# ProPrj__B__2024-10-28.net
KiCad netlist of a schematic drawn in EasyEDA Pro
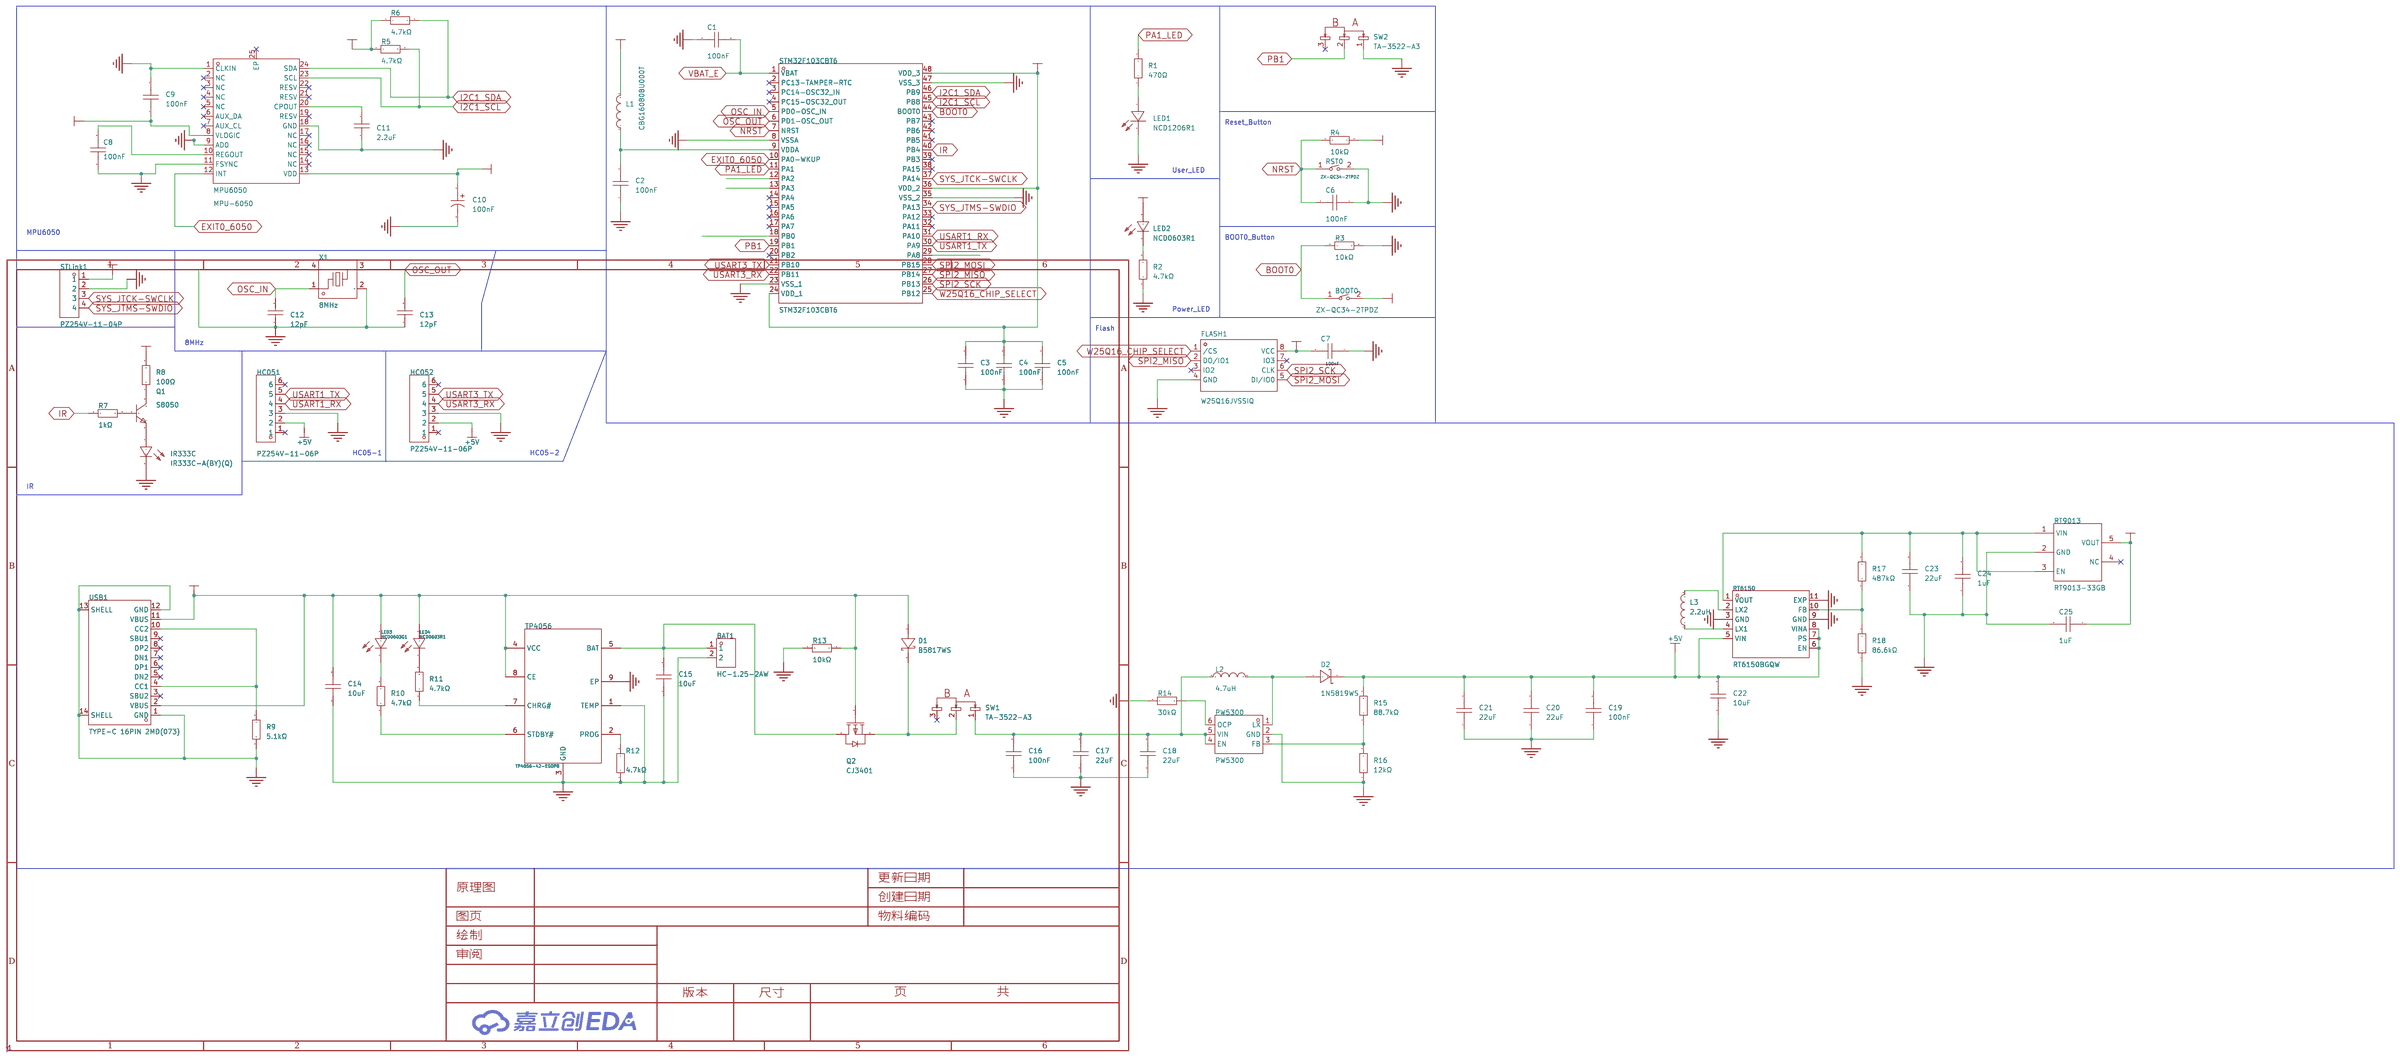
[diagram p0: schematic sheet]

(export (version "E")
  (design (tool "Eeschema 10.0.6"))
  (components
    (comp (ref "BAT1")
      (value "HC-1.25-2AW")
      (footprint "easyedapro:CONN-TH_2P-P1.25_HCTL_HC-1.25-2AW")
      (fields (field (name "Manufacturer") "HCTL(华灿天禄)"))
      (libsource (lib "easyedapro") (part "HC-1.25-2AW"))
    )
    (comp (ref "BOOT0")
      (value "ZX-QC34-2TPDZ")
      (footprint "easyedapro:KEY-SMD_L3.9-W3.0-LS5.0-EH")
      (fields (field (name "Manufacturer") "Megastar(兆星)"))
      (libsource (lib "easyedapro") (part "ZX-QC34-2TPDZ"))
    )
    (comp (ref "C1")
      (value "100nF")
      (footprint "easyedapro:C0603")
      (description "容值:100nF;精度:±10%;额定电压:50V;材质(温度系数):X7R;")
      (fields
        (field (name "Manufacturer Part") "CC0603KRX7R9BB104")
        (field (name "Manufacturer") "YAGEO(国巨)")
      )
      (libsource (lib "easyedapro") (part "CC0603KRX7R9BB104"))
    )
    (comp (ref "C2")
      (value "100nF")
      (footprint "easyedapro:C0603")
      (description "容值:100nF;精度:±10%;额定电压:50V;材质(温度系数):X7R;")
      (fields
        (field (name "Manufacturer Part") "CC0603KRX7R9BB104")
        (field (name "Manufacturer") "YAGEO(国巨)")
      )
      (libsource (lib "easyedapro") (part "CC0603KRX7R9BB104"))
    )
    (comp (ref "C3")
      (value "100nF")
      (footprint "easyedapro:C0603")
      (description "容值:100nF;精度:±10%;额定电压:50V;材质(温度系数):X7R;")
      (fields
        (field (name "Manufacturer Part") "CC0603KRX7R9BB104")
        (field (name "Manufacturer") "YAGEO(国巨)")
      )
      (libsource (lib "easyedapro") (part "CC0603KRX7R9BB104"))
    )
    (comp (ref "C4")
      (value "100nF")
      (footprint "easyedapro:C0603")
      (description "容值:100nF;精度:±10%;额定电压:50V;材质(温度系数):X7R;")
      (fields
        (field (name "Manufacturer Part") "CC0603KRX7R9BB104")
        (field (name "Manufacturer") "YAGEO(国巨)")
      )
      (libsource (lib "easyedapro") (part "CC0603KRX7R9BB104"))
    )
    (comp (ref "C5")
      (value "100nF")
      (footprint "easyedapro:C0603")
      (description "容值:100nF;精度:±10%;额定电压:50V;材质(温度系数):X7R;")
      (fields
        (field (name "Manufacturer Part") "CC0603KRX7R9BB104")
        (field (name "Manufacturer") "YAGEO(国巨)")
      )
      (libsource (lib "easyedapro") (part "CC0603KRX7R9BB104"))
    )
    (comp (ref "C6")
      (value "100nF")
      (footprint "easyedapro:C0603")
      (description "容值:100nF;精度:±10%;额定电压:50V;材质(温度系数):X7R;")
      (fields
        (field (name "Manufacturer Part") "CC0603KRX7R9BB104")
        (field (name "Manufacturer") "YAGEO(国巨)")
      )
      (libsource (lib "easyedapro") (part "CC0603KRX7R9BB104"))
    )
    (comp (ref "C7")
      (value "100nF")
      (footprint "easyedapro:C0603")
      (description "容值:100nF;精度:±10%;额定电压:50V;材质(温度系数):X7R;")
      (fields
        (field (name "Manufacturer Part") "CC0603KRX7R9BB104")
        (field (name "Manufacturer") "YAGEO(国巨)")
      )
      (libsource (lib "easyedapro") (part "CC0603KRX7R9BB104"))
    )
    (comp (ref "C8")
      (value "100nF")
      (footprint "easyedapro:C0603")
      (description "容值:100nF;精度:±10%;额定电压:50V;材质(温度系数):X7R;")
      (fields
        (field (name "Manufacturer Part") "CC0603KRX7R9BB104")
        (field (name "Manufacturer") "YAGEO(国巨)")
      )
      (libsource (lib "easyedapro") (part "CC0603KRX7R9BB104"))
    )
    (comp (ref "C9")
      (value "100nF")
      (footprint "easyedapro:C0603")
      (description "容值:100nF;精度:±10%;额定电压:50V;材质(温度系数):X7R;")
      (fields
        (field (name "Manufacturer Part") "CC0603KRX7R9BB104")
        (field (name "Manufacturer") "YAGEO(国巨)")
      )
      (libsource (lib "easyedapro") (part "CC0603KRX7R9BB104"))
    )
    (comp (ref "C10")
      (value "100nF")
      (footprint "easyedapro:CAP-SMD_L3.2-W1.6-FD")
      (description "容值:100nF;精度:±20%;额定电压:50V;等效串联电阻:20Ω;")
      (fields (field (name "Manufacturer Part") "T491A104M050AT") (field (name "Manufacturer") "KEMET(基美)"))
      (libsource (lib "easyedapro") (part "T491A104M050AT"))
    )
    (comp (ref "C11")
      (value "2.2uF")
      (footprint "easyedapro:C0603")
      (description "容值:2.2uF;精度:±10%;额定电压:16V;材质(温度系数):X5R;")
      (fields
        (field (name "Manufacturer Part") "CL10A225KO8NNNC")
        (field (name "Manufacturer") "SAMSUNG(三星)")
      )
      (libsource (lib "easyedapro") (part "CL10A225KO8NNNC"))
    )
    (comp (ref "C12")
      (value "12pF")
      (footprint "easyedapro:C0603")
      (description "容值:12pF;精度:±5%;额定电压:50V;材质(温度系数):C0G;")
      (fields
        (field (name "Manufacturer Part") "CL10C120JB8NNNC")
        (field (name "Manufacturer") "SAMSUNG(三星)")
      )
      (libsource (lib "easyedapro") (part "CL10C120JB8NNNC"))
    )
    (comp (ref "C13")
      (value "12pF")
      (footprint "easyedapro:C0603")
      (description "容值:12pF;精度:±5%;额定电压:50V;材质(温度系数):C0G;")
      (fields
        (field (name "Manufacturer Part") "CL10C120JB8NNNC")
        (field (name "Manufacturer") "SAMSUNG(三星)")
      )
      (libsource (lib "easyedapro") (part "CL10C120JB8NNNC"))
    )
    (comp (ref "C14")
      (value "10uF")
      (footprint "easyedapro:C0603")
      (description "容值:10uF;精度:±20%;额定电压:16V;材质(温度系数):X5R;")
      (fields
        (field (name "Manufacturer Part") "HGC0603R5106M160NTHJ")
        (field (name "Manufacturer") "Chinocera(华瓷)")
      )
      (libsource (lib "easyedapro") (part "HGC0603R5106M160NTHJ"))
    )
    (comp (ref "C15")
      (value "10uF")
      (footprint "easyedapro:C0603")
      (description "容值:10uF;精度:±20%;额定电压:16V;材质(温度系数):X5R;")
      (fields
        (field (name "Manufacturer Part") "HGC0603R5106M160NTHJ")
        (field (name "Manufacturer") "Chinocera(华瓷)")
      )
      (libsource (lib "easyedapro") (part "HGC0603R5106M160NTHJ"))
    )
    (comp (ref "C16")
      (value "100nF")
      (footprint "easyedapro:C0603")
      (description "容值:100nF;精度:±10%;额定电压:50V;材质(温度系数):X7R;")
      (fields
        (field (name "Manufacturer Part") "CGA0603X7R104K500JT")
        (field (name "Manufacturer") "HRE(芯声)")
      )
      (libsource (lib "easyedapro") (part "cga0603x7r104k500jt"))
    )
    (comp (ref "C17")
      (value "22uF")
      (footprint "easyedapro:C0805")
      (description "容值:22uF;精度:±20%;额定电压:35V;材质(温度系数):X5R;")
      (fields
        (field (name "Manufacturer Part") "CGA0603X5R226M160JT")
        (field (name "Manufacturer") "HRE(芯声)")
      )
      (libsource (lib "easyedapro") (part "CGA0805X5R226M350MT"))
    )
    (comp (ref "C18")
      (value "22uF")
      (footprint "easyedapro:C0805")
      (description "容值:22uF;精度:±20%;额定电压:35V;材质(温度系数):X5R;")
      (fields
        (field (name "Manufacturer Part") "CGA0603X5R226M160JT")
        (field (name "Manufacturer") "HRE(芯声)")
      )
      (libsource (lib "easyedapro") (part "CGA0805X5R226M350MT"))
    )
    (comp (ref "C19")
      (value "100nF")
      (footprint "easyedapro:C0603")
      (description "容值:100nF;精度:±10%;额定电压:50V;材质(温度系数):X7R;")
      (fields
        (field (name "Manufacturer Part") "CGA0603X7R104K500JT")
        (field (name "Manufacturer") "HRE(芯声)")
      )
      (libsource (lib "easyedapro") (part "cga0603x7r104k500jt"))
    )
    (comp (ref "C20")
      (value "22uF")
      (footprint "easyedapro:C0805")
      (description "容值:22uF;精度:±20%;额定电压:35V;材质(温度系数):X5R;")
      (fields
        (field (name "Manufacturer Part") "CGA0603X5R226M160JT")
        (field (name "Manufacturer") "HRE(芯声)")
      )
      (libsource (lib "easyedapro") (part "CGA0805X5R226M350MT"))
    )
    (comp (ref "C21")
      (value "22uF")
      (footprint "easyedapro:C0805")
      (description "容值:22uF;精度:±20%;额定电压:35V;材质(温度系数):X5R;")
      (fields
        (field (name "Manufacturer Part") "CGA0603X5R226M160JT")
        (field (name "Manufacturer") "HRE(芯声)")
      )
      (libsource (lib "easyedapro") (part "CGA0805X5R226M350MT"))
    )
    (comp (ref "C22")
      (value "10uF")
      (footprint "easyedapro:C0603")
      (description "容值:10uF;精度:±20%;额定电压:16V;材质(温度系数):X5R;")
      (fields
        (field (name "Manufacturer Part") "HGC0603R5106M160NTHJ")
        (field (name "Manufacturer") "Chinocera(华瓷)")
      )
      (libsource (lib "easyedapro") (part "HGC0603R5106M160NTHJ"))
    )
    (comp (ref "C23")
      (value "22uF")
      (footprint "easyedapro:C0603")
      (description "容值:22uF;精度:±20%;额定电压:16V;材质(温度系数):X5R;")
      (fields
        (field (name "Manufacturer Part") "CGA0603X5R226M160JT")
        (field (name "Manufacturer") "HRE(芯声)")
      )
      (libsource (lib "easyedapro") (part "CGA0603X5R226M160JT"))
    )
    (comp (ref "C24")
      (value "1uF")
      (footprint "easyedapro:C0603")
      (description "容值:1uF;精度:±10%;额定电压:16V;材质(温度系数):X5R;")
      (fields
        (field (name "Manufacturer Part") "CGA0603X5R105K160JT")
        (field (name "Manufacturer") "HRE(芯声)")
      )
      (libsource (lib "easyedapro") (part "CGA0603X5R105K160JT"))
    )
    (comp (ref "C25")
      (value "1uF")
      (footprint "easyedapro:C0603")
      (description "容值:1uF;精度:±10%;额定电压:16V;材质(温度系数):X5R;")
      (fields
        (field (name "Manufacturer Part") "CGA0603X5R105K160JT")
        (field (name "Manufacturer") "HRE(芯声)")
      )
      (libsource (lib "easyedapro") (part "CGA0603X5R105K160JT"))
    )
    (comp (ref "D1")
      (value "B5817WS")
      (footprint "easyedapro:SOD-323_L1.7-W1.3-LS2.5-FD")
      (description "二极管配置:独立式;正向压降(Vf):450mV@1.0A;直流反向耐压(Vr):20V;平均整流电流(Io):1A;")
      (fields (field (name "Manufacturer") "宏迦橙"))
      (libsource (lib "easyedapro") (part "B5817WS_C7420329"))
    )
    (comp (ref "D2")
      (value "1N5819WS")
      (footprint "easyedapro:SMB_L4.6-W3.6-LS5.3-RD")
      (description "正向压降(Vf):500mV@3A;直流反向耐压(Vr):40V;平均整流电流(Io):3A;")
      (fields (field (name "Manufacturer") "Hottech(合科泰)"))
      (libsource (lib "easyedapro") (part "SS34_C266556"))
    )
    (comp (ref "FLASH1")
      (value "W25Q16JVSSIQ")
      (footprint "easyedapro:SOIC-8_L5.3-W5.3-P1.27-LS8.0-BL")
      (description "（与C82317为同一颗物料，只是编带方式不一样。）3V 16Mbit Serial Flash Memory with dual/quad SPI")
      (fields (field (name "Manufacturer") "WINBOND(华邦)"))
      (libsource (lib "easyedapro") (part "W25Q16JVSSIQTR"))
    )
    (comp (ref "HC051")
      (value "PZ254V-11-06P")
      (footprint "easyedapro:HDR-TH_6P-P2.54-V-M")
      (fields (field (name "Manufacturer") "XFCN(兴飞)"))
      (libsource (lib "easyedapro") (part "PZ254V-11-06P"))
    )
    (comp (ref "HC052")
      (value "PZ254V-11-06P")
      (footprint "easyedapro:HDR-TH_6P-P2.54-V-M")
      (fields (field (name "Manufacturer") "XFCN(兴飞)"))
      (libsource (lib "easyedapro") (part "PZ254V-11-06P"))
    )
    (comp (ref "IR333C")
      (value "IR333C-A(BY)(Q)")
      (footprint "easyedapro:LED-TH_BD5.0-P2.54-FD")
      (description "波长:940nm;")
      (fields (field (name "Manufacturer") "EVERLIGHT(亿光)"))
      (libsource (lib "easyedapro") (part "ir333c-a(by)(q)"))
    )
    (comp (ref "L1")
      (value "CBG160808U000T")
      (footprint "easyedapro:L0603")
      (description "标称阻抗@测试频率:0Ω@100MHz;直流电阻(RDC):100mΩ;")
      (fields (field (name "Manufacturer") "FH(风华)"))
      (libsource (lib "easyedapro") (part "CBG160808U000T"))
    )
    (comp (ref "L2")
      (value "4.7uH")
      (footprint "easyedapro:IND-SMD_L5.4-W5.2_FXL0530")
      (description "电感值:4.7uH;精度:±20%;额定电流:4.5A;饱和电流(Isat):5A;类型:一体成型电感;")
      (fields
        (field (name "Manufacturer Part") "FTC252010S4R7MBCA")
        (field (name "Manufacturer") "cjiang(长江微电)")
      )
      (libsource (lib "easyedapro") (part "FXL0530-4R7-M"))
    )
    (comp (ref "L3")
      (value "2.2uH")
      (footprint "easyedapro:IND-SMD_L2.5-W2.0_MHCHL2520")
      (description "电感值:2.2uH;精度:±20%;额定电流:3A;饱和电流(Isat):3.8A;类型:一体成型电感;")
      (fields
        (field (name "Manufacturer Part") "FTC252012S2R2MBCA")
        (field (name "Manufacturer") "cjiang(长江微电)")
      )
      (libsource (lib "easyedapro") (part "FTC252012S2R2MBCA"))
    )
    (comp (ref "LED1")
      (value "NCD1206R1")
      (footprint "easyedapro:LED1206-R-RD_RED")
      (fields (field (name "Manufacturer") "国星光电"))
      (libsource (lib "easyedapro") (part "FC-3215HRK-620D"))
    )
    (comp (ref "LED2")
      (value "NCD0603R1")
      (footprint "easyedapro:LED0603-RD_RED")
      (fields (field (name "Manufacturer") "国星光电"))
      (libsource (lib "easyedapro") (part "FC-DA1608HRK-620D"))
    )
    (comp (ref "LED3")
      (value "NCD0603G1")
      (footprint "easyedapro:led0603-rd_1")
      (fields (field (name "Manufacturer") "国星光电"))
      (libsource (lib "easyedapro") (part "FC-D1608UGK-520D10"))
    )
    (comp (ref "LED4")
      (value "NCD0603R1")
      (footprint "easyedapro:led0603-rd_1")
      (fields (field (name "Manufacturer") "国星光电"))
      (libsource (lib "easyedapro") (part "FC-D1608UGK-520D10"))
    )
    (comp (ref "MPU6050")
      (value "MPU-6050")
      (footprint "easyedapro:QFN-24_L4.0-W4.0-P0.50-BL-EP2.7")
      (description "传感器类型:加速度计陀螺仪;")
      (fields (field (name "Manufacturer") "TDK InvenSense(应美盛)"))
      (libsource (lib "easyedapro") (part "MPU-6050_C24112"))
    )
    (comp (ref "PW5300")
      (value "PW5300")
      (footprint "easyedapro:SOT-23-6_L2.9-W1.6-P0.95-LS2.8-BL")
      (libsource (lib "easyedapro") (part "PW5300"))
    )
    (comp (ref "Q1")
      (value "S8050")
      (footprint "easyedapro:SOT-23-3_L2.9-W1.6-P1.90-LS2.8-BR")
      (description "晶体管类型:NPN;集电极电流(Ic):500mA;集射极击穿电压(Vceo):25V;功率(Pd):300mW;")
      (fields (field (name "Manufacturer") "Hottech(合科泰)"))
      (libsource (lib "easyedapro") (part "S8050_C181158"))
    )
    (comp (ref "Q2")
      (value "CJ3401")
      (footprint "easyedapro:SOT-23-3_L2.9-W1.6-P1.90-LS2.8-BR")
      (fields (field (name "Manufacturer") "CJ(江苏长电/长晶)"))
      (libsource (lib "easyedapro") (part "CJ3401"))
    )
    (comp (ref "R1")
      (value "470Ω")
      (footprint "easyedapro:R0603")
      (description "电阻类型:厚膜电阻;阻值:470Ω;精度:±1%;功率:100mW;最大工作电压:75V;温度系数:±100ppm/°C;")
      (fields
        (field (name "Manufacturer Part") "0603WAF4700T5E")
        (field (name "Manufacturer") "UNI-ROYAL(厚声)")
      )
      (libsource (lib "easyedapro") (part "0603WAF4700T5E"))
    )
    (comp (ref "R2")
      (value "4.7kΩ")
      (footprint "easyedapro:R0603")
      (description "电阻类型:厚膜电阻;阻值:4.7kΩ;精度:±1%;功率:100mW;最大工作电压:75V;温度系数:±100ppm/°C;")
      (fields
        (field (name "Manufacturer Part") "0603WAF4701T5E")
        (field (name "Manufacturer") "UNI-ROYAL(厚声)")
      )
      (libsource (lib "easyedapro") (part "0603WAF4701T5E"))
    )
    (comp (ref "R3")
      (value "10kΩ")
      (footprint "easyedapro:R0603")
      (description "电阻类型:厚膜电阻;阻值:10kΩ;精度:±1%;功率:100mW;最大工作电压:75V;温度系数:±100ppm/°C;")
      (fields
        (field (name "Manufacturer Part") "0603WAF1002T5E")
        (field (name "Manufacturer") "UNI-ROYAL(厚声)")
      )
      (libsource (lib "easyedapro") (part "0603WAF1002T5E"))
    )
    (comp (ref "R4")
      (value "10kΩ")
      (footprint "easyedapro:R0603")
      (description "电阻类型:厚膜电阻;阻值:10kΩ;精度:±1%;功率:100mW;最大工作电压:75V;温度系数:±100ppm/°C;")
      (fields
        (field (name "Manufacturer Part") "0603WAF1002T5E")
        (field (name "Manufacturer") "UNI-ROYAL(厚声)")
      )
      (libsource (lib "easyedapro") (part "0603WAF1002T5E"))
    )
    (comp (ref "R5")
      (value "4.7kΩ")
      (footprint "easyedapro:R0603")
      (description "电阻类型:厚膜电阻;阻值:4.7kΩ;精度:±1%;功率:100mW;最大工作电压:75V;温度系数:±100ppm/°C;")
      (fields
        (field (name "Manufacturer Part") "0603WAF4701T5E")
        (field (name "Manufacturer") "UNI-ROYAL(厚声)")
      )
      (libsource (lib "easyedapro") (part "0603WAF4701T5E"))
    )
    (comp (ref "R6")
      (value "4.7kΩ")
      (footprint "easyedapro:R0603")
      (description "电阻类型:厚膜电阻;阻值:4.7kΩ;精度:±1%;功率:100mW;最大工作电压:75V;温度系数:±100ppm/°C;")
      (fields
        (field (name "Manufacturer Part") "0603WAF4701T5E")
        (field (name "Manufacturer") "UNI-ROYAL(厚声)")
      )
      (libsource (lib "easyedapro") (part "0603WAF4701T5E"))
    )
    (comp (ref "R7")
      (value "1kΩ")
      (footprint "easyedapro:R0603")
      (description "电阻类型:厚膜电阻;阻值:1kΩ;精度:±1%;功率:100mW;最大工作电压:75V;温度系数:±100ppm/°C;")
      (fields
        (field (name "Manufacturer Part") "0603WAF1001T5E")
        (field (name "Manufacturer") "UNI-ROYAL(厚声)")
      )
      (libsource (lib "easyedapro") (part "0603WAF1001T5E"))
    )
    (comp (ref "R8")
      (value "100Ω")
      (footprint "easyedapro:R0603")
      (description "电阻类型:厚膜电阻;阻值:100Ω;精度:±1%;功率:100mW;最大工作电压:75V;温度系数:±200ppm/°C;")
      (fields
        (field (name "Manufacturer Part") "0603WAF1000T5E")
        (field (name "Manufacturer") "UNI-ROYAL(厚声)")
      )
      (libsource (lib "easyedapro") (part "0603WAF1000T5E"))
    )
    (comp (ref "R9")
      (value "5.1kΩ")
      (footprint "easyedapro:R0603")
      (description "电阻类型:厚膜电阻;阻值:5.1kΩ;精度:±1%;功率:100mW;最大工作电压:75V;温度系数:±100ppm/°C;")
      (fields
        (field (name "Manufacturer Part") "0603WAF5101T5E")
        (field (name "Manufacturer") "UNI-ROYAL(厚声)")
      )
      (libsource (lib "easyedapro") (part "0603WAF5101T5E"))
    )
    (comp (ref "R10")
      (value "4.7kΩ")
      (footprint "easyedapro:R0603")
      (description "电阻类型:厚膜电阻;阻值:4.7kΩ;精度:±1%;功率:100mW;最大工作电压:75V;温度系数:±100ppm/°C;")
      (fields
        (field (name "Manufacturer Part") "0603WAF4701T5E")
        (field (name "Manufacturer") "UNI-ROYAL(厚声)")
      )
      (libsource (lib "easyedapro") (part "0603WAF4701T5E"))
    )
    (comp (ref "R11")
      (value "4.7kΩ")
      (footprint "easyedapro:R0603")
      (description "电阻类型:厚膜电阻;阻值:4.7kΩ;精度:±1%;功率:100mW;最大工作电压:75V;温度系数:±100ppm/°C;")
      (fields
        (field (name "Manufacturer Part") "0603WAF4701T5E")
        (field (name "Manufacturer") "UNI-ROYAL(厚声)")
      )
      (libsource (lib "easyedapro") (part "0603WAF4701T5E"))
    )
    (comp (ref "R12")
      (value "4.7kΩ")
      (footprint "easyedapro:R0603")
      (description "电阻类型:厚膜电阻;阻值:4.7kΩ;精度:±1%;功率:100mW;最大工作电压:75V;温度系数:±100ppm/°C;")
      (fields
        (field (name "Manufacturer Part") "0603WAF4701T5E")
        (field (name "Manufacturer") "UNI-ROYAL(厚声)")
      )
      (libsource (lib "easyedapro") (part "0603WAF4701T5E"))
    )
    (comp (ref "R13")
      (value "10kΩ")
      (footprint "easyedapro:R0603")
      (description "电阻类型:厚膜电阻;阻值:10kΩ;精度:±1%;功率:100mW;最大工作电压:75V;温度系数:±100ppm/°C;")
      (fields
        (field (name "Manufacturer Part") "0603WAF1002T5E")
        (field (name "Manufacturer") "UNI-ROYAL(厚声)")
      )
      (libsource (lib "easyedapro") (part "0603WAF1002T5E"))
    )
    (comp (ref "R14")
      (value "30kΩ")
      (footprint "easyedapro:R0603")
      (description "电阻类型:厚膜电阻;阻值:30kΩ;精度:±1%;功率:100mW;最大工作电压:75V;温度系数:±100ppm/°C;")
      (fields
        (field (name "Manufacturer Part") "0603WAF3002T5E")
        (field (name "Manufacturer") "UNI-ROYAL(厚声)")
      )
      (libsource (lib "easyedapro") (part "0603WAF3002T5E"))
    )
    (comp (ref "R15")
      (value "88.7kΩ")
      (footprint "easyedapro:R0603")
      (fields (field (name "Manufacturer Part") "RCT0388K7FLF") (field (name "Manufacturer") "HKR(香港电阻)"))
      (libsource (lib "easyedapro") (part "电阻"))
    )
    (comp (ref "R16")
      (value "12kΩ")
      (footprint "easyedapro:R0603")
      (description "电阻类型:厚膜电阻;阻值:12kΩ;精度:±1%;功率:100mW;最大工作电压:75V;温度系数:±100ppm/°C;")
      (fields
        (field (name "Manufacturer Part") "0603WAF1202T5E")
        (field (name "Manufacturer") "UNI-ROYAL(厚声)")
      )
      (libsource (lib "easyedapro") (part "0603WAF1202T5E"))
    )
    (comp (ref "R17")
      (value "487kΩ")
      (footprint "easyedapro:R0603")
      (description "电阻类型:厚膜电阻;阻值:487kΩ;精度:±1%;功率:100mW;最大工作电压:75V;温度系数:±100ppm/°C;")
      (fields
        (field (name "Manufacturer Part") "0603WAF4873T5E")
        (field (name "Manufacturer") "UNI-ROYAL(厚声)")
      )
      (libsource (lib "easyedapro") (part "0603WAF4873T5E"))
    )
    (comp (ref "R18")
      (value "86.6kΩ")
      (footprint "easyedapro:R0603")
      (description "电阻类型:厚膜电阻;阻值:86.6kΩ;精度:±1%;功率:100mW;最大工作电压:75V;温度系数:±100ppm/°C;")
      (fields
        (field (name "Manufacturer Part") "0603WAF8662T5E")
        (field (name "Manufacturer") "UNI-ROYAL(厚声)")
      )
      (libsource (lib "easyedapro") (part "0603WAF8662T5E"))
    )
    (comp (ref "RST0")
      (value "ZX-QC34-2TPDZ")
      (footprint "easyedapro:KEY-SMD_L3.9-W3.0-LS5.0-EH")
      (fields (field (name "Manufacturer") "Megastar(兆星)"))
      (libsource (lib "easyedapro") (part "ZX-QC34-2TPDZ"))
    )
    (comp (ref "RT6150")
      (value "RT6150BGQW")
      (footprint "easyedapro:WSON-10_L2.5-W2.5-P0.50-BL-EP")
      (description "功能类型:升降压型;输入电压:1.8V~5.5V;输出电压:1.8V~5.5V;输出电流(最大值):800mA;")
      (fields (field (name "Manufacturer") "RICHTEK(立锜)"))
      (libsource (lib "easyedapro") (part "RT6150BGQW"))
    )
    (comp (ref "RT9013")
      (value "RT9013-33GB")
      (footprint "easyedapro:SOT-23-5_L3.0-W1.7-P0.95-LS2.8-BL")
      (description "输出类型:固定;最大输入电压:5.5V;输出电压:3.3V;最大输出电流:500mA;电源纹波抑制比(PSRR):50dB@(10kHz);输出极性:正极;")
      (fields (field (name "Manufacturer") "RICHTEK(立锜)"))
      (libsource (lib "easyedapro") (part "RT9013-33GB"))
    )
    (comp (ref "STLink1")
      (value "PZ254V-11-04P")
      (footprint "easyedapro:HDR-TH_4P-P2.54-V-M")
      (fields (field (name "Manufacturer") "XFCN(兴飞)"))
      (libsource (lib "easyedapro") (part "PZ254V-11-04P_C2691448"))
    )
    (comp (ref "STM32F103CBT6")
      (value "STM32F103CBT6")
      (fields (field (name "Manufacturer") "ST(意法半导体)"))
      (libsource (lib "easyedapro") (part "APM32F103CBT6"))
    )
    (comp (ref "SW1")
      (value "TA-3522-A3")
      (footprint "easyedapro:SW-TH_3P-L9.1-W3.5-P2.50-A3")
      (fields (field (name "Manufacturer") "Yuandi(元迪)"))
      (libsource (lib "easyedapro") (part "TA-3522-A3"))
    )
    (comp (ref "SW2")
      (value "TA-3522-A3")
      (footprint "easyedapro:SW-TH_3P-L9.1-W3.5-P2.50-A3")
      (fields (field (name "Manufacturer") "Yuandi(元迪)"))
      (libsource (lib "easyedapro") (part "TA-3522-A3"))
    )
    (comp (ref "TP4056")
      (value "TP4056-42-ESOP8")
      (footprint "easyedapro:ESOP-8_L4.9-W3.9-P1.27-LS6.0-BL-EP")
      (description "锂电池充电芯片 42代表电池满电电压4.2V。")
      (fields (field (name "Manufacturer") "TOPPOWER(南京拓微)"))
      (libsource (lib "easyedapro") (part "TP4056"))
    )
    (comp (ref "USB1")
      (value "TYPE-C 16PIN 2MD(073)")
      (footprint "easyedapro:USB-C-SMD_TYPE-C-6PIN-2MD-073")
      (description "连接器类型:Type-C;标准:USB 3.1;公母:母;安装方式:卧贴;触点数量:16P;端口数量:1;额定电流 - 电源:5A;工作温度范围:-25°C~+85°C;")
      (fields (field (name "Manufacturer") "SHOU HAN(首韩)"))
      (libsource (lib "easyedapro") (part "TYPE-C 16PIN 2MD(073)"))
    )
    (comp (ref "X1")
      (value "8MHz")
      (footprint "easyedapro:OSC-SMD_4P-L3.2-W2.5-BL")
      (description "晶振类型:贴片晶振;频率:8MHz;常温频差:±10ppm;外接负载电容:12pF;频率稳定度(全温):±20ppm;")
      (fields (field (name "Manufacturer Part") "X32258MOB4SI") (field (name "Manufacturer") "YXC(扬兴晶振)"))
      (libsource (lib "easyedapro") (part "x32258mob4si"))
    )
  )
  (nets
    (net (code "1") (name "+5V") (class "Default")
      (node (ref "C19") (pin "2") (pinfunction "2_2") (pintype "unspecified"))
      (node (ref "C20") (pin "2") (pinfunction "2_2") (pintype "unspecified"))
      (node (ref "C21") (pin "2") (pinfunction "2_2") (pintype "unspecified"))
      (node (ref "C22") (pin "2") (pinfunction "2_2") (pintype "unspecified"))
      (node (ref "D2") (pin "1") (pinfunction "C_1") (pintype "unspecified"))
      (node (ref "HC051") (pin "2") (pinfunction "2_2") (pintype "unspecified"))
      (node (ref "HC052") (pin "2") (pinfunction "2_2") (pintype "unspecified"))
      (node (ref "R15") (pin "2") (pinfunction "2_2") (pintype "input"))
      (node (ref "RT6150") (pin "5") (pinfunction "VIN_5") (pintype "input"))
      (node (ref "RT6150") (pin "6") (pinfunction "EN_6") (pintype "input"))
      (node (ref "RT6150") (pin "7") (pinfunction "PS_7") (pintype "input"))
      (node (ref "RT6150") (pin "8") (pinfunction "VINA_8") (pintype "input"))
    )
    (net (code "2") (name "3V3") (class "Default")
      (node (ref "BOOT0") (pin "2") (pinfunction "2_2") (pintype "unspecified"))
      (node (ref "C10") (pin "1") (pinfunction "1_1") (pintype "input"))
      (node (ref "C25") (pin "1") (pinfunction "1_1") (pintype "unspecified"))
      (node (ref "C3") (pin "2") (pinfunction "2_2") (pintype "unspecified"))
      (node (ref "C4") (pin "2") (pinfunction "2_2") (pintype "unspecified"))
      (node (ref "C5") (pin "2") (pinfunction "2_2") (pintype "unspecified"))
      (node (ref "C7") (pin "2") (pinfunction "2_2") (pintype "unspecified"))
      (node (ref "C9") (pin "1") (pinfunction "1_1") (pintype "unspecified"))
      (node (ref "FLASH1") (pin "8") (pinfunction "VCC_8") (pintype "unspecified"))
      (node (ref "L1") (pin "2") (pinfunction "2_2") (pintype "unspecified"))
      (node (ref "LED2") (pin "2") (pinfunction "A_2") (pintype "input"))
      (node (ref "MPU6050") (pin "13") (pinfunction "VDD_13") (pintype "unspecified"))
      (node (ref "MPU6050") (pin "8") (pinfunction "VLOGIC_8") (pintype "unspecified"))
      (node (ref "R4") (pin "2") (pinfunction "2_2") (pintype "input"))
      (node (ref "R5") (pin "1") (pinfunction "1_1") (pintype "input"))
      (node (ref "R6") (pin "1") (pinfunction "1_1") (pintype "input"))
      (node (ref "R8") (pin "2") (pinfunction "2_2") (pintype "input"))
      (node (ref "RT9013") (pin "5") (pinfunction "VOUT_5") (pintype "unspecified"))
      (node (ref "STLink1") (pin "1") (pinfunction "1_1") (pintype "unspecified"))
      (node (ref "STM32F103CBT6") (pin "24") (pinfunction "VDD_1_24") (pintype "unspecified"))
      (node (ref "STM32F103CBT6") (pin "36") (pinfunction "VDD_2_36") (pintype "unspecified"))
      (node (ref "STM32F103CBT6") (pin "48") (pinfunction "VDD_3_48") (pintype "unspecified"))
    )
    (net (code "3") (name "BOOT0") (class "Default")
      (node (ref "BOOT0") (pin "1") (pinfunction "1_1") (pintype "unspecified"))
      (node (ref "R3") (pin "1") (pinfunction "1_1") (pintype "input"))
      (node (ref "STM32F103CBT6") (pin "44") (pinfunction "BOOT0_44") (pintype "unspecified"))
    )
    (net (code "4") (name "EXIT0_6050") (class "Default")
      (node (ref "MPU6050") (pin "12") (pinfunction "INT_12") (pintype "unspecified"))
      (node (ref "STM32F103CBT6") (pin "10") (pinfunction "PA0-WKUP_10") (pintype "unspecified"))
    )
    (net (code "5") (name "GND") (class "Default")
      (node (ref "BAT1") (pin "2") (pinfunction "2_2") (pintype "unspecified"))
      (node (ref "C1") (pin "1") (pinfunction "1_1") (pintype "unspecified"))
      (node (ref "C10") (pin "2") (pinfunction "2_2") (pintype "input"))
      (node (ref "C11") (pin "1") (pinfunction "1_1") (pintype "input"))
      (node (ref "C12") (pin "1") (pinfunction "1_1") (pintype "input"))
      (node (ref "C13") (pin "1") (pinfunction "1_1") (pintype "input"))
      (node (ref "C14") (pin "1") (pinfunction "1_1") (pintype "unspecified"))
      (node (ref "C15") (pin "1") (pinfunction "1_1") (pintype "unspecified"))
      (node (ref "C16") (pin "1") (pinfunction "1_1") (pintype "unspecified"))
      (node (ref "C17") (pin "1") (pinfunction "1_1") (pintype "unspecified"))
      (node (ref "C18") (pin "1") (pinfunction "1_1") (pintype "unspecified"))
      (node (ref "C19") (pin "1") (pinfunction "1_1") (pintype "unspecified"))
      (node (ref "C2") (pin "1") (pinfunction "1_1") (pintype "unspecified"))
      (node (ref "C20") (pin "1") (pinfunction "1_1") (pintype "unspecified"))
      (node (ref "C21") (pin "1") (pinfunction "1_1") (pintype "unspecified"))
      (node (ref "C22") (pin "1") (pinfunction "1_1") (pintype "unspecified"))
      (node (ref "C23") (pin "1") (pinfunction "1_1") (pintype "unspecified"))
      (node (ref "C24") (pin "1") (pinfunction "1_1") (pintype "unspecified"))
      (node (ref "C25") (pin "2") (pinfunction "2_2") (pintype "unspecified"))
      (node (ref "C3") (pin "1") (pinfunction "1_1") (pintype "unspecified"))
      (node (ref "C4") (pin "1") (pinfunction "1_1") (pintype "unspecified"))
      (node (ref "C5") (pin "1") (pinfunction "1_1") (pintype "unspecified"))
      (node (ref "C6") (pin "1") (pinfunction "1_1") (pintype "unspecified"))
      (node (ref "C7") (pin "1") (pinfunction "1_1") (pintype "unspecified"))
      (node (ref "C8") (pin "1") (pinfunction "1_1") (pintype "unspecified"))
      (node (ref "C9") (pin "2") (pinfunction "2_2") (pintype "unspecified"))
      (node (ref "FLASH1") (pin "4") (pinfunction "GND_4") (pintype "unspecified"))
      (node (ref "HC051") (pin "3") (pinfunction "3_3") (pintype "unspecified"))
      (node (ref "HC052") (pin "3") (pinfunction "3_3") (pintype "unspecified"))
      (node (ref "IR333C") (pin "2") (pinfunction "C_2") (pintype "input"))
      (node (ref "LED1") (pin "2") (pinfunction "K_2") (pintype "unspecified"))
      (node (ref "MPU6050") (pin "1") (pinfunction "CLKIN_1") (pintype "unspecified"))
      (node (ref "MPU6050") (pin "11") (pinfunction "FSYNC_11") (pintype "unspecified"))
      (node (ref "MPU6050") (pin "18") (pinfunction "GND_18") (pintype "unspecified"))
      (node (ref "MPU6050") (pin "9") (pinfunction "AD0_9") (pintype "unspecified"))
      (node (ref "PW5300") (pin "2") (pinfunction "GND_2") (pintype "unspecified"))
      (node (ref "R12") (pin "1") (pinfunction "1_1") (pintype "input"))
      (node (ref "R13") (pin "1") (pinfunction "1_1") (pintype "input"))
      (node (ref "R14") (pin "1") (pinfunction "1_1") (pintype "input"))
      (node (ref "R16") (pin "1") (pinfunction "1_1") (pintype "input"))
      (node (ref "R18") (pin "1") (pinfunction "1_1") (pintype "input"))
      (node (ref "R2") (pin "1") (pinfunction "1_1") (pintype "input"))
      (node (ref "R3") (pin "2") (pinfunction "2_2") (pintype "input"))
      (node (ref "R9") (pin "1") (pinfunction "1_1") (pintype "input"))
      (node (ref "RST0") (pin "2") (pinfunction "2_2") (pintype "unspecified"))
      (node (ref "RT6150") (pin "11") (pinfunction "EXP_11") (pintype "input"))
      (node (ref "RT6150") (pin "3") (pinfunction "GND_3") (pintype "input"))
      (node (ref "RT6150") (pin "9") (pinfunction "GND_9") (pintype "input"))
      (node (ref "RT9013") (pin "2") (pinfunction "GND_2") (pintype "unspecified"))
      (node (ref "STLink1") (pin "2") (pinfunction "2_2") (pintype "unspecified"))
      (node (ref "STM32F103CBT6") (pin "23") (pinfunction "VSS_1_23") (pintype "unspecified"))
      (node (ref "STM32F103CBT6") (pin "35") (pinfunction "VSS_2_35") (pintype "unspecified"))
      (node (ref "STM32F103CBT6") (pin "47") (pinfunction "VSS_3_47") (pintype "unspecified"))
      (node (ref "STM32F103CBT6") (pin "8") (pinfunction "VSSA_8") (pintype "unspecified"))
      (node (ref "SW2") (pin "1") (pinfunction "1_1") (pintype "unspecified"))
      (node (ref "TP4056") (pin "1") (pinfunction "TEMP_1") (pintype "unspecified"))
      (node (ref "TP4056") (pin "3") (pinfunction "GND_3") (pintype "unspecified"))
      (node (ref "TP4056") (pin "9") (pinfunction "EP_9") (pintype "unspecified"))
      (node (ref "USB1") (pin "1") (pinfunction "GND_1") (pintype "unspecified"))
      (node (ref "USB1") (pin "12") (pinfunction "GND_12") (pintype "unspecified"))
      (node (ref "USB1") (pin "13") (pinfunction "SHELL_13") (pintype "unspecified"))
      (node (ref "USB1") (pin "14") (pinfunction "SHELL_14") (pintype "unspecified"))
      (node (ref "X1") (pin "2") (pinfunction "GND_2") (pintype "input"))
      (node (ref "X1") (pin "4") (pinfunction "GND_4") (pintype "input"))
    )
    (net (code "6") (name "I2C1_SCL") (class "Default")
      (node (ref "MPU6050") (pin "23") (pinfunction "SCL_23") (pintype "unspecified"))
      (node (ref "R5") (pin "2") (pinfunction "2_2") (pintype "input"))
      (node (ref "STM32F103CBT6") (pin "45") (pinfunction "PB8_45") (pintype "unspecified"))
    )
    (net (code "7") (name "I2C1_SDA") (class "Default")
      (node (ref "MPU6050") (pin "24") (pinfunction "SDA_24") (pintype "unspecified"))
      (node (ref "R6") (pin "2") (pinfunction "2_2") (pintype "input"))
      (node (ref "STM32F103CBT6") (pin "46") (pinfunction "PB9_46") (pintype "unspecified"))
    )
    (net (code "8") (name "IR") (class "Default")
      (node (ref "R7") (pin "1") (pinfunction "1_1") (pintype "input"))
      (node (ref "STM32F103CBT6") (pin "40") (pinfunction "PB4_40") (pintype "unspecified"))
    )
    (net (code "9") (name "NRST") (class "Default")
      (node (ref "C6") (pin "2") (pinfunction "2_2") (pintype "unspecified"))
      (node (ref "R4") (pin "1") (pinfunction "1_1") (pintype "input"))
      (node (ref "RST0") (pin "1") (pinfunction "1_1") (pintype "unspecified"))
      (node (ref "STM32F103CBT6") (pin "7") (pinfunction "NRST_7") (pintype "unspecified"))
    )
    (net (code "10") (name "Net-(D1-K)") (class "Default")
      (node (ref "D1") (pin "2") (pinfunction "K_2") (pintype "unspecified"))
      (node (ref "Q2") (pin "2") (pinfunction "S_2") (pintype "unspecified"))
      (node (ref "SW1") (pin "2") (pinfunction "2_2") (pintype "unspecified"))
    )
    (net (code "11") (name "Net-(D2-A)") (class "Default")
      (node (ref "D2") (pin "2") (pinfunction "A_2") (pintype "unspecified"))
      (node (ref "L2") (pin "2") (pinfunction "2_2") (pintype "unspecified"))
      (node (ref "PW5300") (pin "1") (pinfunction "LX_1") (pintype "unspecified"))
    )
    (net (code "12") (name "Net-(IR333C-A)") (class "Default")
      (node (ref "IR333C") (pin "1") (pinfunction "A_1") (pintype "input"))
      (node (ref "Q1") (pin "2") (pinfunction "2_2") (pintype "input"))
    )
    (net (code "13") (name "Net-(LED1-A)") (class "Default")
      (node (ref "LED1") (pin "1") (pinfunction "A_1") (pintype "unspecified"))
      (node (ref "R1") (pin "1") (pinfunction "1_1") (pintype "input"))
    )
    (net (code "14") (name "Net-(LED2-K)") (class "Default")
      (node (ref "LED2") (pin "1") (pinfunction "K_1") (pintype "input"))
      (node (ref "R2") (pin "2") (pinfunction "2_2") (pintype "input"))
    )
    (net (code "15") (name "Net-(LED3-K)") (class "Default")
      (node (ref "LED3") (pin "1") (pinfunction "K_1") (pintype "input"))
      (node (ref "R10") (pin "2") (pinfunction "2_2") (pintype "input"))
    )
    (net (code "16") (name "Net-(LED4-K)") (class "Default")
      (node (ref "LED4") (pin "1") (pinfunction "K_1") (pintype "input"))
      (node (ref "R11") (pin "2") (pinfunction "2_2") (pintype "input"))
    )
    (net (code "17") (name "Net-(MPU6050-CPOUT)") (class "Default")
      (node (ref "C11") (pin "2") (pinfunction "2_2") (pintype "input"))
      (node (ref "MPU6050") (pin "20") (pinfunction "CPOUT_20") (pintype "unspecified"))
    )
    (net (code "18") (name "Net-(MPU6050-REGOUT)") (class "Default")
      (node (ref "C8") (pin "2") (pinfunction "2_2") (pintype "unspecified"))
      (node (ref "MPU6050") (pin "10") (pinfunction "REGOUT_10") (pintype "unspecified"))
    )
    (net (code "19") (name "Net-(PW5300-EN)") (class "Default")
      (node (ref "C16") (pin "2") (pinfunction "2_2") (pintype "unspecified"))
      (node (ref "C17") (pin "2") (pinfunction "2_2") (pintype "unspecified"))
      (node (ref "C18") (pin "2") (pinfunction "2_2") (pintype "unspecified"))
      (node (ref "L2") (pin "1") (pinfunction "1_1") (pintype "unspecified"))
      (node (ref "PW5300") (pin "4") (pinfunction "EN_4") (pintype "unspecified"))
      (node (ref "PW5300") (pin "5") (pinfunction "VIN_5") (pintype "unspecified"))
      (node (ref "SW1") (pin "1") (pinfunction "1_1") (pintype "unspecified"))
    )
    (net (code "20") (name "Net-(PW5300-FB)") (class "Default")
      (node (ref "PW5300") (pin "3") (pinfunction "FB_3") (pintype "unspecified"))
      (node (ref "R15") (pin "1") (pinfunction "1_1") (pintype "input"))
      (node (ref "R16") (pin "2") (pinfunction "2_2") (pintype "input"))
    )
    (net (code "21") (name "Net-(PW5300-OCP)") (class "Default")
      (node (ref "PW5300") (pin "6") (pinfunction "OCP_6") (pintype "unspecified"))
      (node (ref "R14") (pin "2") (pinfunction "2_2") (pintype "input"))
    )
    (net (code "22") (name "Net-(Q1-Pad1)") (class "Default")
      (node (ref "Q1") (pin "1") (pinfunction "1_1") (pintype "input"))
      (node (ref "R7") (pin "2") (pinfunction "2_2") (pintype "input"))
    )
    (net (code "23") (name "Net-(Q1-Pad3)") (class "Default")
      (node (ref "Q1") (pin "3") (pinfunction "3_3") (pintype "input"))
      (node (ref "R8") (pin "1") (pinfunction "1_1") (pintype "input"))
    )
    (net (code "24") (name "Net-(Q2-D)") (class "Default")
      (node (ref "BAT1") (pin "1") (pinfunction "1_1") (pintype "unspecified"))
      (node (ref "C15") (pin "2") (pinfunction "2_2") (pintype "unspecified"))
      (node (ref "Q2") (pin "3") (pinfunction "D_3") (pintype "unspecified"))
      (node (ref "TP4056") (pin "5") (pinfunction "BAT_5") (pintype "unspecified"))
    )
    (net (code "25") (name "Net-(RT6150-FB)") (class "Default")
      (node (ref "R17") (pin "1") (pinfunction "1_1") (pintype "input"))
      (node (ref "R18") (pin "2") (pinfunction "2_2") (pintype "input"))
      (node (ref "RT6150") (pin "10") (pinfunction "FB_10") (pintype "input"))
    )
    (net (code "26") (name "Net-(RT6150-LX1)") (class "Default")
      (node (ref "L3") (pin "1") (pinfunction "1_1") (pintype "unspecified"))
      (node (ref "RT6150") (pin "4") (pinfunction "LX1_4") (pintype "input"))
    )
    (net (code "27") (name "Net-(RT6150-LX2)") (class "Default")
      (node (ref "L3") (pin "2") (pinfunction "2_2") (pintype "unspecified"))
      (node (ref "RT6150") (pin "2") (pinfunction "LX2_2") (pintype "input"))
    )
    (net (code "28") (name "Net-(RT6150-VOUT)") (class "Default")
      (node (ref "C23") (pin "2") (pinfunction "2_2") (pintype "unspecified"))
      (node (ref "C24") (pin "2") (pinfunction "2_2") (pintype "unspecified"))
      (node (ref "R17") (pin "2") (pinfunction "2_2") (pintype "input"))
      (node (ref "RT6150") (pin "1") (pinfunction "VOUT_1") (pintype "input"))
      (node (ref "RT9013") (pin "1") (pinfunction "VIN_1") (pintype "unspecified"))
      (node (ref "RT9013") (pin "3") (pinfunction "EN_3") (pintype "unspecified"))
    )
    (net (code "29") (name "Net-(STM32F103CBT6-VDDA)") (class "Default")
      (node (ref "C2") (pin "2") (pinfunction "2_2") (pintype "unspecified"))
      (node (ref "L1") (pin "1") (pinfunction "1_1") (pintype "unspecified"))
      (node (ref "STM32F103CBT6") (pin "9") (pinfunction "VDDA_9") (pintype "unspecified"))
    )
    (net (code "30") (name "Net-(TP4056-CHRG#)") (class "Default")
      (node (ref "R11") (pin "1") (pinfunction "1_1") (pintype "input"))
      (node (ref "TP4056") (pin "7") (pinfunction "CHRG#_7") (pintype "unspecified"))
    )
    (net (code "31") (name "Net-(TP4056-PROG)") (class "Default")
      (node (ref "R12") (pin "2") (pinfunction "2_2") (pintype "input"))
      (node (ref "TP4056") (pin "2") (pinfunction "PROG_2") (pintype "unspecified"))
    )
    (net (code "32") (name "Net-(TP4056-STDBY#)") (class "Default")
      (node (ref "R10") (pin "1") (pinfunction "1_1") (pintype "input"))
      (node (ref "TP4056") (pin "6") (pinfunction "STDBY#_6") (pintype "unspecified"))
    )
    (net (code "33") (name "Net-(USB1-CC1)") (class "Default")
      (node (ref "R9") (pin "2") (pinfunction "2_2") (pintype "input"))
      (node (ref "USB1") (pin "10") (pinfunction "CC2_10") (pintype "unspecified"))
      (node (ref "USB1") (pin "4") (pinfunction "CC1_4") (pintype "unspecified"))
    )
    (net (code "34") (name "OSC_IN") (class "Default")
      (node (ref "C12") (pin "2") (pinfunction "2_2") (pintype "input"))
      (node (ref "STM32F103CBT6") (pin "5") (pinfunction "PD0-OSC_IN_5") (pintype "unspecified"))
      (node (ref "X1") (pin "1") (pinfunction "1_1") (pintype "input"))
    )
    (net (code "35") (name "OSC_OUT") (class "Default")
      (node (ref "C13") (pin "2") (pinfunction "2_2") (pintype "input"))
      (node (ref "STM32F103CBT6") (pin "6") (pinfunction "PD1-OSC_OUT_6") (pintype "unspecified"))
      (node (ref "X1") (pin "3") (pinfunction "3_3") (pintype "input"))
    )
    (net (code "36") (name "PA1_LED") (class "Default")
      (node (ref "R1") (pin "2") (pinfunction "2_2") (pintype "input"))
      (node (ref "STM32F103CBT6") (pin "11") (pinfunction "PA1_11") (pintype "unspecified"))
    )
    (net (code "37") (name "PB1") (class "Default")
      (node (ref "STM32F103CBT6") (pin "19") (pinfunction "PB1_19") (pintype "unspecified"))
      (node (ref "SW2") (pin "2") (pinfunction "2_2") (pintype "unspecified"))
    )
    (net (code "38") (name "SPI2_MISO") (class "Default")
      (node (ref "FLASH1") (pin "2") (pinfunction "DO/IO1_2") (pintype "unspecified"))
      (node (ref "STM32F103CBT6") (pin "27") (pinfunction "PB14_27") (pintype "unspecified"))
    )
    (net (code "39") (name "SPI2_MOSI") (class "Default")
      (node (ref "FLASH1") (pin "5") (pinfunction "DI/IO0_5") (pintype "unspecified"))
      (node (ref "STM32F103CBT6") (pin "28") (pinfunction "PB15_28") (pintype "unspecified"))
    )
    (net (code "40") (name "SPI2_SCK") (class "Default")
      (node (ref "FLASH1") (pin "6") (pinfunction "CLK_6") (pintype "unspecified"))
      (node (ref "STM32F103CBT6") (pin "26") (pinfunction "PB13_26") (pintype "unspecified"))
    )
    (net (code "41") (name "SYS_JTCK-SWCLK") (class "Default")
      (node (ref "STLink1") (pin "3") (pinfunction "3_3") (pintype "unspecified"))
      (node (ref "STM32F103CBT6") (pin "37") (pinfunction "PA14_37") (pintype "unspecified"))
    )
    (net (code "42") (name "SYS_JTMS-SWDIO") (class "Default")
      (node (ref "STLink1") (pin "4") (pinfunction "4_4") (pintype "unspecified"))
      (node (ref "STM32F103CBT6") (pin "34") (pinfunction "PA13_34") (pintype "unspecified"))
    )
    (net (code "43") (name "USART1_RX") (class "Default")
      (node (ref "HC051") (pin "4") (pinfunction "4_4") (pintype "unspecified"))
      (node (ref "STM32F103CBT6") (pin "31") (pinfunction "PA10_31") (pintype "unspecified"))
    )
    (net (code "44") (name "USART1_TX") (class "Default")
      (node (ref "HC051") (pin "5") (pinfunction "5_5") (pintype "unspecified"))
      (node (ref "STM32F103CBT6") (pin "30") (pinfunction "PA9_30") (pintype "unspecified"))
    )
    (net (code "45") (name "USART3_RX") (class "Default")
      (node (ref "HC052") (pin "4") (pinfunction "4_4") (pintype "unspecified"))
      (node (ref "STM32F103CBT6") (pin "22") (pinfunction "PB11_22") (pintype "unspecified"))
    )
    (net (code "46") (name "USART3_TX") (class "Default")
      (node (ref "HC052") (pin "5") (pinfunction "5_5") (pintype "unspecified"))
      (node (ref "STM32F103CBT6") (pin "21") (pinfunction "PB10_21") (pintype "unspecified"))
    )
    (net (code "47") (name "VBAT_E") (class "Default")
      (node (ref "C1") (pin "2") (pinfunction "2_2") (pintype "unspecified"))
      (node (ref "STM32F103CBT6") (pin "1") (pinfunction "VBAT_1") (pintype "unspecified"))
    )
    (net (code "48") (name "VCC_USB") (class "Default")
      (node (ref "C14") (pin "2") (pinfunction "2_2") (pintype "unspecified"))
      (node (ref "D1") (pin "1") (pinfunction "A_1") (pintype "unspecified"))
      (node (ref "LED3") (pin "2") (pinfunction "A_2") (pintype "input"))
      (node (ref "LED4") (pin "2") (pinfunction "A_2") (pintype "input"))
      (node (ref "Q2") (pin "1") (pinfunction "G_1") (pintype "unspecified"))
      (node (ref "R13") (pin "2") (pinfunction "2_2") (pintype "input"))
      (node (ref "TP4056") (pin "4") (pinfunction "VCC_4") (pintype "unspecified"))
      (node (ref "TP4056") (pin "8") (pinfunction "CE_8") (pintype "unspecified"))
      (node (ref "USB1") (pin "11") (pinfunction "VBUS_11") (pintype "unspecified"))
      (node (ref "USB1") (pin "2") (pinfunction "VBUS_2") (pintype "unspecified"))
    )
    (net (code "49") (name "W25Q16_CHIP_SELECT") (class "Default")
      (node (ref "FLASH1") (pin "1") (pinfunction "/CS_1") (pintype "unspecified"))
      (node (ref "STM32F103CBT6") (pin "25") (pinfunction "PB12_25") (pintype "unspecified"))
    )
    (net (code "50") (name "unconnected-(FLASH1-IO2-Pad3)") (class "Default")
      (node (ref "FLASH1") (pin "3") (pinfunction "IO2_3") (pintype "unspecified+no_connect"))
    )
    (net (code "51") (name "unconnected-(FLASH1-IO3-Pad7)") (class "Default")
      (node (ref "FLASH1") (pin "7") (pinfunction "IO3_7") (pintype "unspecified+no_connect"))
    )
    (net (code "52") (name "unconnected-(HC051-Pad1)") (class "Default")
      (node (ref "HC051") (pin "1") (pinfunction "1_1") (pintype "unspecified+no_connect"))
    )
    (net (code "53") (name "unconnected-(HC051-Pad6)") (class "Default")
      (node (ref "HC051") (pin "6") (pinfunction "6_6") (pintype "unspecified+no_connect"))
    )
    (net (code "54") (name "unconnected-(HC052-Pad1)") (class "Default")
      (node (ref "HC052") (pin "1") (pinfunction "1_1") (pintype "unspecified+no_connect"))
    )
    (net (code "55") (name "unconnected-(HC052-Pad6)") (class "Default")
      (node (ref "HC052") (pin "6") (pinfunction "6_6") (pintype "unspecified+no_connect"))
    )
    (net (code "56") (name "unconnected-(MPU6050-AUX_CL-Pad7)") (class "Default")
      (node (ref "MPU6050") (pin "7") (pinfunction "AUX_CL_7") (pintype "unspecified+no_connect"))
    )
    (net (code "57") (name "unconnected-(MPU6050-AUX_DA-Pad6)") (class "Default")
      (node (ref "MPU6050") (pin "6") (pinfunction "AUX_DA_6") (pintype "unspecified+no_connect"))
    )
    (net (code "58") (name "unconnected-(MPU6050-EP-Pad25)") (class "Default")
      (node (ref "MPU6050") (pin "25") (pinfunction "EP_25") (pintype "unspecified+no_connect"))
    )
    (net (code "59") (name "unconnected-(MPU6050-NC-Pad2)") (class "Default")
      (node (ref "MPU6050") (pin "2") (pinfunction "NC_2") (pintype "unspecified+no_connect"))
    )
    (net (code "60") (name "unconnected-(MPU6050-NC-Pad3)") (class "Default")
      (node (ref "MPU6050") (pin "3") (pinfunction "NC_3") (pintype "unspecified+no_connect"))
    )
    (net (code "61") (name "unconnected-(MPU6050-NC-Pad4)") (class "Default")
      (node (ref "MPU6050") (pin "4") (pinfunction "NC_4") (pintype "unspecified+no_connect"))
    )
    (net (code "62") (name "unconnected-(MPU6050-NC-Pad5)") (class "Default")
      (node (ref "MPU6050") (pin "5") (pinfunction "NC_5") (pintype "unspecified+no_connect"))
    )
    (net (code "63") (name "unconnected-(MPU6050-NC-Pad14)") (class "Default")
      (node (ref "MPU6050") (pin "14") (pinfunction "NC_14") (pintype "unspecified+no_connect"))
    )
    (net (code "64") (name "unconnected-(MPU6050-NC-Pad15)") (class "Default")
      (node (ref "MPU6050") (pin "15") (pinfunction "NC_15") (pintype "unspecified+no_connect"))
    )
    (net (code "65") (name "unconnected-(MPU6050-NC-Pad16)") (class "Default")
      (node (ref "MPU6050") (pin "16") (pinfunction "NC_16") (pintype "unspecified+no_connect"))
    )
    (net (code "66") (name "unconnected-(MPU6050-NC-Pad17)") (class "Default")
      (node (ref "MPU6050") (pin "17") (pinfunction "NC_17") (pintype "unspecified+no_connect"))
    )
    (net (code "67") (name "unconnected-(MPU6050-RESV-Pad19)") (class "Default")
      (node (ref "MPU6050") (pin "19") (pinfunction "RESV_19") (pintype "unspecified+no_connect"))
    )
    (net (code "68") (name "unconnected-(MPU6050-RESV-Pad21)") (class "Default")
      (node (ref "MPU6050") (pin "21") (pinfunction "RESV_21") (pintype "unspecified+no_connect"))
    )
    (net (code "69") (name "unconnected-(MPU6050-RESV-Pad22)") (class "Default")
      (node (ref "MPU6050") (pin "22") (pinfunction "RESV_22") (pintype "unspecified+no_connect"))
    )
    (net (code "70") (name "unconnected-(RT9013-NC-Pad4)") (class "Default")
      (node (ref "RT9013") (pin "4") (pinfunction "NC_4") (pintype "unspecified+no_connect"))
    )
    (net (code "71") (name "unconnected-(STM32F103CBT6-PA2-Pad12)") (class "Default")
      (node (ref "STM32F103CBT6") (pin "12") (pinfunction "PA2_12") (pintype "unspecified"))
    )
    (net (code "72") (name "unconnected-(STM32F103CBT6-PA3-Pad13)") (class "Default")
      (node (ref "STM32F103CBT6") (pin "13") (pinfunction "PA3_13") (pintype "unspecified"))
    )
    (net (code "73") (name "unconnected-(STM32F103CBT6-PA4-Pad14)") (class "Default")
      (node (ref "STM32F103CBT6") (pin "14") (pinfunction "PA4_14") (pintype "unspecified+no_connect"))
    )
    (net (code "74") (name "unconnected-(STM32F103CBT6-PA5-Pad15)") (class "Default")
      (node (ref "STM32F103CBT6") (pin "15") (pinfunction "PA5_15") (pintype "unspecified+no_connect"))
    )
    (net (code "75") (name "unconnected-(STM32F103CBT6-PA6-Pad16)") (class "Default")
      (node (ref "STM32F103CBT6") (pin "16") (pinfunction "PA6_16") (pintype "unspecified+no_connect"))
    )
    (net (code "76") (name "unconnected-(STM32F103CBT6-PA7-Pad17)") (class "Default")
      (node (ref "STM32F103CBT6") (pin "17") (pinfunction "PA7_17") (pintype "unspecified+no_connect"))
    )
    (net (code "77") (name "unconnected-(STM32F103CBT6-PA8-Pad29)") (class "Default")
      (node (ref "STM32F103CBT6") (pin "29") (pinfunction "PA8_29") (pintype "unspecified"))
    )
    (net (code "78") (name "unconnected-(STM32F103CBT6-PA11-Pad32)") (class "Default")
      (node (ref "STM32F103CBT6") (pin "32") (pinfunction "PA11_32") (pintype "unspecified+no_connect"))
    )
    (net (code "79") (name "unconnected-(STM32F103CBT6-PA12-Pad33)") (class "Default")
      (node (ref "STM32F103CBT6") (pin "33") (pinfunction "PA12_33") (pintype "unspecified+no_connect"))
    )
    (net (code "80") (name "unconnected-(STM32F103CBT6-PA15-Pad38)") (class "Default")
      (node (ref "STM32F103CBT6") (pin "38") (pinfunction "PA15_38") (pintype "unspecified+no_connect"))
    )
    (net (code "81") (name "unconnected-(STM32F103CBT6-PB0-Pad18)") (class "Default")
      (node (ref "STM32F103CBT6") (pin "18") (pinfunction "PB0_18") (pintype "unspecified"))
    )
    (net (code "82") (name "unconnected-(STM32F103CBT6-PB2-Pad20)") (class "Default")
      (node (ref "STM32F103CBT6") (pin "20") (pinfunction "PB2_20") (pintype "unspecified+no_connect"))
    )
    (net (code "83") (name "unconnected-(STM32F103CBT6-PB3-Pad39)") (class "Default")
      (node (ref "STM32F103CBT6") (pin "39") (pinfunction "PB3_39") (pintype "unspecified+no_connect"))
    )
    (net (code "84") (name "unconnected-(STM32F103CBT6-PB5-Pad41)") (class "Default")
      (node (ref "STM32F103CBT6") (pin "41") (pinfunction "PB5_41") (pintype "unspecified+no_connect"))
    )
    (net (code "85") (name "unconnected-(STM32F103CBT6-PB6-Pad42)") (class "Default")
      (node (ref "STM32F103CBT6") (pin "42") (pinfunction "PB6_42") (pintype "unspecified+no_connect"))
    )
    (net (code "86") (name "unconnected-(STM32F103CBT6-PB7-Pad43)") (class "Default")
      (node (ref "STM32F103CBT6") (pin "43") (pinfunction "PB7_43") (pintype "unspecified+no_connect"))
    )
    (net (code "87") (name "unconnected-(STM32F103CBT6-PC13-TAMPER-RTC-Pad2)") (class "Default")
      (node (ref "STM32F103CBT6") (pin "2") (pinfunction "PC13-TAMPER-RTC_2") (pintype "unspecified+no_connect"))
    )
    (net (code "88") (name "unconnected-(STM32F103CBT6-PC14-OSC32_IN-Pad3)") (class "Default")
      (node (ref "STM32F103CBT6") (pin "3") (pinfunction "PC14-OSC32_IN_3") (pintype "unspecified+no_connect"))
    )
    (net (code "89") (name "unconnected-(STM32F103CBT6-PC15-OSC32_OUT-Pad4)") (class "Default")
      (node (ref "STM32F103CBT6") (pin "4") (pinfunction "PC15-OSC32_OUT_4") (pintype "unspecified+no_connect"))
    )
    (net (code "90") (name "unconnected-(SW1-Pad3)") (class "Default")
      (node (ref "SW1") (pin "3") (pinfunction "3_3") (pintype "unspecified+no_connect"))
    )
    (net (code "91") (name "unconnected-(SW2-Pad3)") (class "Default")
      (node (ref "SW2") (pin "3") (pinfunction "3_3") (pintype "unspecified+no_connect"))
    )
    (net (code "92") (name "unconnected-(USB1-DN1-Pad7)") (class "Default")
      (node (ref "USB1") (pin "7") (pinfunction "DN1_7") (pintype "unspecified+no_connect"))
    )
    (net (code "93") (name "unconnected-(USB1-DN2-Pad5)") (class "Default")
      (node (ref "USB1") (pin "5") (pinfunction "DN2_5") (pintype "unspecified+no_connect"))
    )
    (net (code "94") (name "unconnected-(USB1-DP1-Pad6)") (class "Default")
      (node (ref "USB1") (pin "6") (pinfunction "DP1_6") (pintype "unspecified+no_connect"))
    )
    (net (code "95") (name "unconnected-(USB1-DP2-Pad8)") (class "Default")
      (node (ref "USB1") (pin "8") (pinfunction "DP2_8") (pintype "unspecified+no_connect"))
    )
    (net (code "96") (name "unconnected-(USB1-SBU1-Pad9)") (class "Default")
      (node (ref "USB1") (pin "9") (pinfunction "SBU1_9") (pintype "unspecified+no_connect"))
    )
    (net (code "97") (name "unconnected-(USB1-SBU2-Pad3)") (class "Default")
      (node (ref "USB1") (pin "3") (pinfunction "SBU2_3") (pintype "unspecified+no_connect"))
    )
  )
)
